# Connectors.net
KiCad netlist of a schematic drawn in Altium Designer
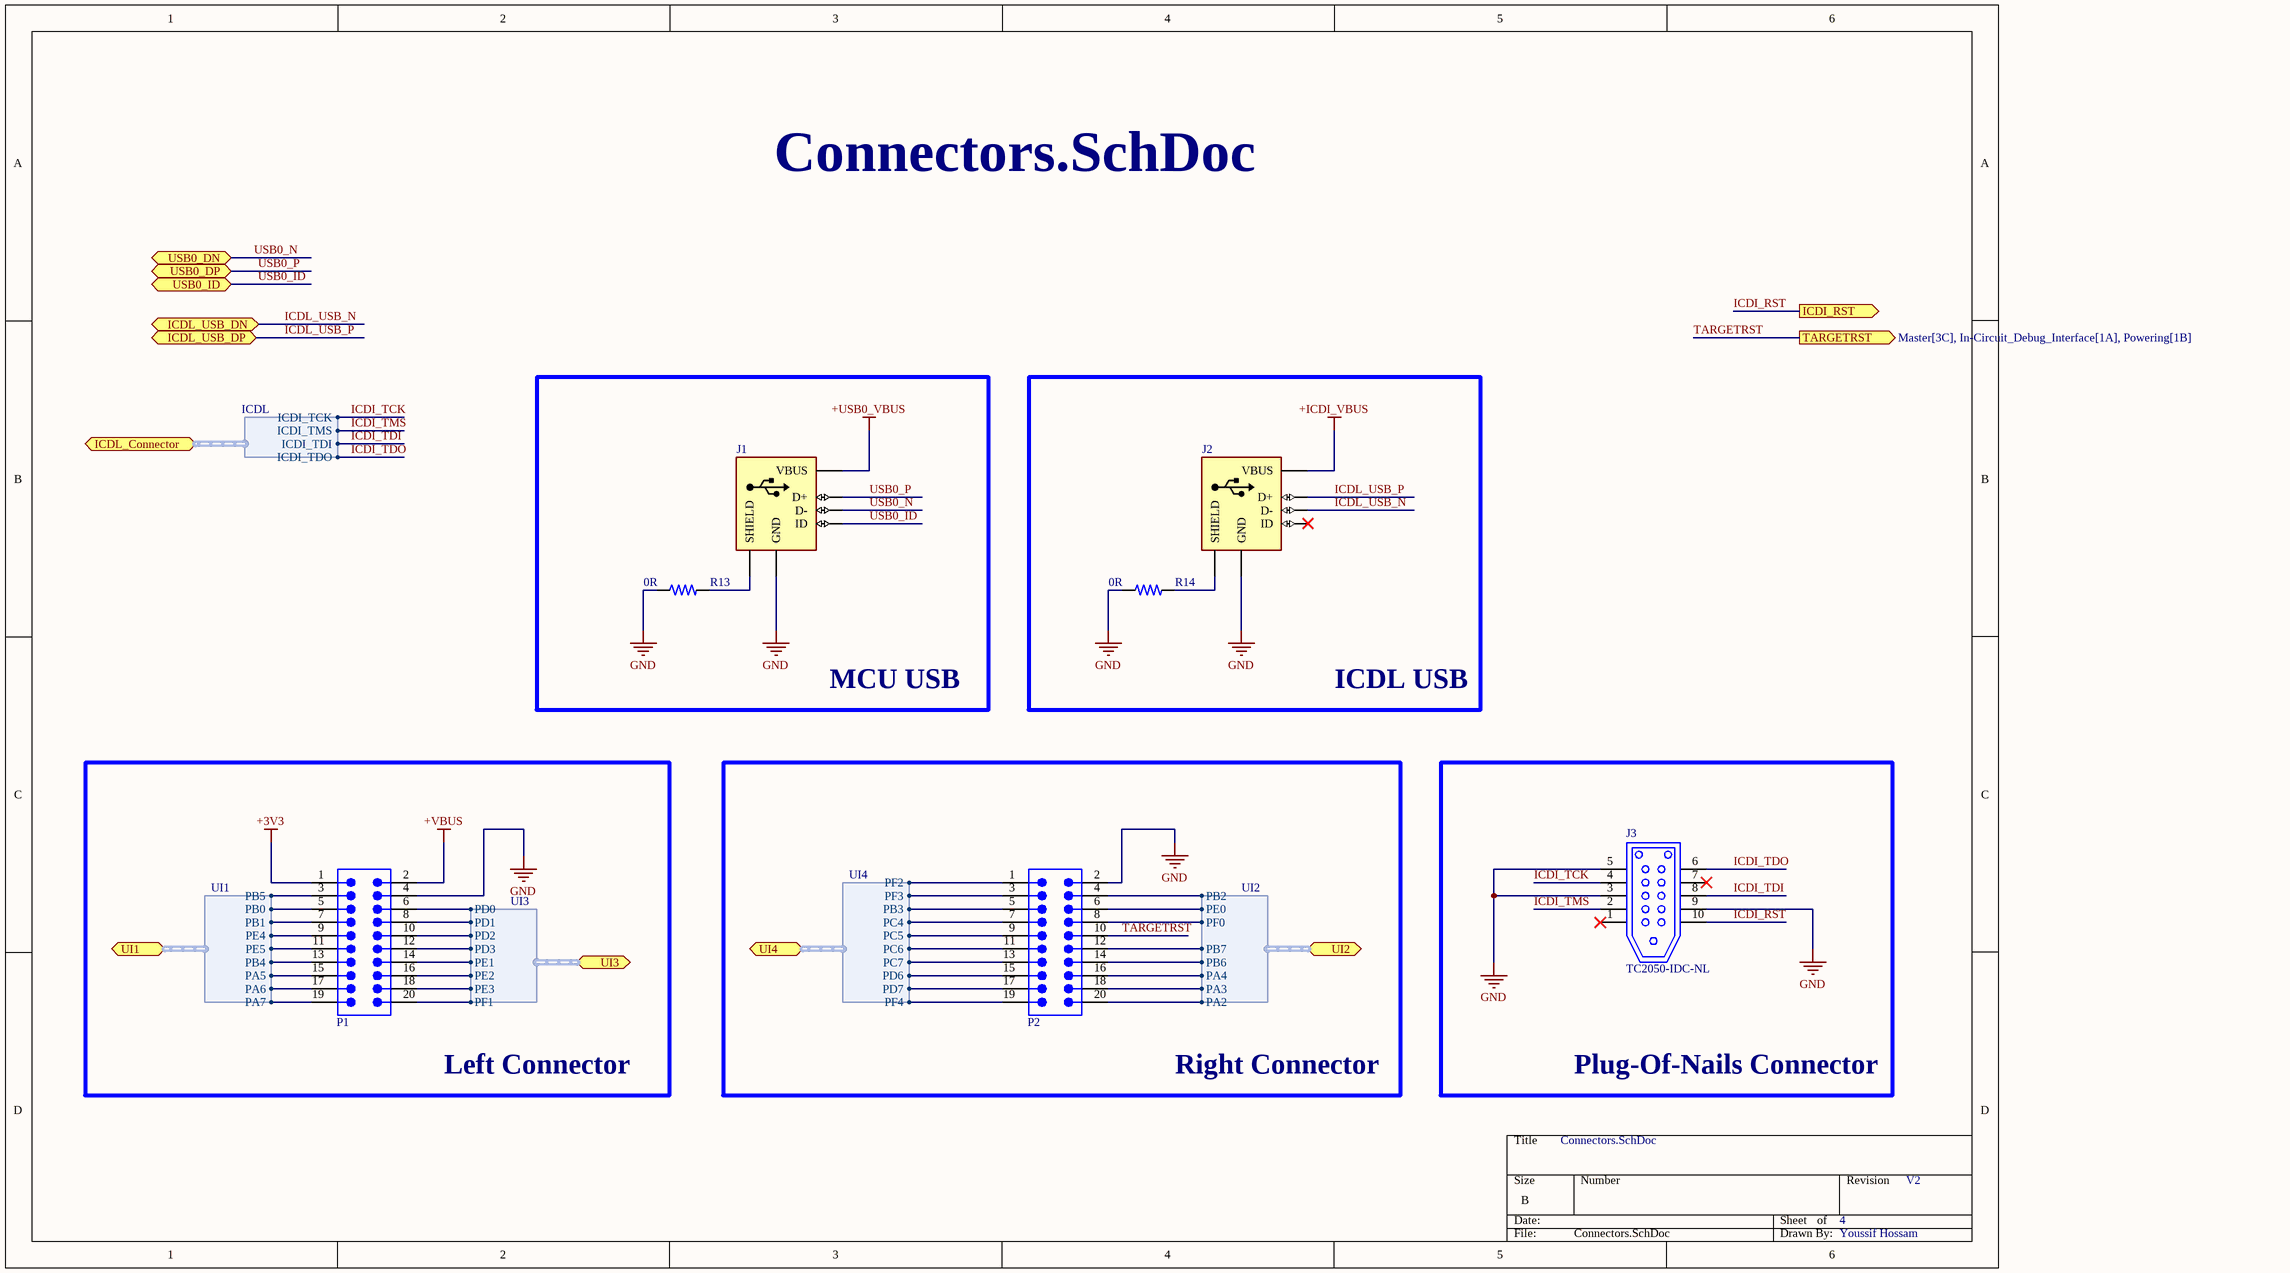
[diagram p0: Connectors.SchDoc]

(export (version "E")
  (design (tool "Eeschema 10.0.6"))
  (components
    (comp (ref "J1")
      (value "USB3085-XX-X_REVD")
      (footprint "GCT_USB3085-XX-X_REVD")
      (description "USB - micro AB USB 2.0 Receptacle Connector 5 Position Surface Mount, Right Angle")
      (fields (field (name "MF") "Global Connector Technology") (field (name "MP") "USB3085-30-A"))
      (libsource (lib "Integrated_Library") (part "USB3085-XX-X_REVD"))
    )
    (comp (ref "J2")
      (value "USB3085-XX-X_REVD")
      (footprint "GCT_USB3085-XX-X_REVD")
      (description "USB - micro AB USB 2.0 Receptacle Connector 5 Position Surface Mount, Right Angle")
      (fields (field (name "MF") "Global Connector Technology") (field (name "MP") "USB3085-30-A"))
      (libsource (lib "Integrated_Library") (part "USB3085-XX-X_REVD"))
    )
    (comp (ref "J3")
      (value "TC2050-IDC-NL")
      (footprint "TAG-CONNECT_TC2050-IDC-NL")
      (description "MSP-FET430 Flash Emulation Tool Plug-Of-Nailsâ„¢ Adapter Cable")
      (fields (field (name "MF") "Tag-Connect LLC"))
      (libsource (lib "Integrated_Library") (part "TC2050-IDC-NL"))
    )
    (comp (ref "P1")
      (value "61302021121")
      (footprint "61302021121")
      (description "WR-PHD Pin Header, THT, Vertical, pitch 2.54mm, 2 Row, 20P")
      (fields (field (name "MANUFACTURER") "Wurth Elektronik"))
      (libsource (lib "Altium_WR-PHD_rev24a") (part "61302021121"))
    )
    (comp (ref "P2")
      (value "61302021121")
      (footprint "61302021121")
      (description "WR-PHD Pin Header, THT, Vertical, pitch 2.54mm, 2 Row, 20P")
      (fields (field (name "MANUFACTURER") "Wurth Elektronik"))
      (libsource (lib "Altium_WR-PHD_rev24a") (part "61302021121"))
    )
    (comp (ref "R13")
      (value "0R")
      (footprint "FP-ERA3A-IPC_B")
      (description "Fixed Resistor, Metal Glaze/thick Film, 0.1W, 0ohm, Surface Mount, 0603")
      (fields
        (field (name "MANUFACTURER") "Panasonic")
        (field (name "MANUFACTURER PART NUMBER") "ERJ-3GEY0R00V")
      )
      (libsource (lib "Integrated_Library") (part "0603 SMD RES"))
    )
    (comp (ref "R14")
      (value "0R")
      (footprint "FP-ERA3A-IPC_B")
      (description "Fixed Resistor, Metal Glaze/thick Film, 0.1W, 0ohm, Surface Mount, 0603")
      (fields
        (field (name "MANUFACTURER") "Panasonic")
        (field (name "MANUFACTURER PART NUMBER") "ERJ-3GEY0R00V")
      )
      (libsource (lib "Integrated_Library") (part "0603 SMD RES"))
    )
  )
  (nets
    (net (code "6") (name "+3V3") (class "Default")
      (node (ref "P1") (pin "1") (pinfunction "1_1") (pintype "passive"))
    )
    (net (code "7") (name "+ICDI_VBUS") (class "Default")
      (node (ref "J2") (pin "1") (pinfunction "VBUS_1") (pintype "power_in"))
    )
    (net (code "8") (name "+USB0_VBUS") (class "Default")
      (node (ref "J1") (pin "1") (pinfunction "VBUS_1") (pintype "power_in"))
    )
    (net (code "9") (name "+VBUS") (class "Default")
      (node (ref "P1") (pin "2") (pinfunction "2_2") (pintype "passive"))
    )
    (net (code "10") (name "/ICDI_RST") (class "Default")
      (node (ref "J3") (pin "10") (pinfunction "10_10") (pintype "passive"))
    )
    (net (code "11") (name "/ICDI_TCK") (class "Default")
      (node (ref "J3") (pin "4") (pinfunction "4_4") (pintype "passive"))
    )
    (net (code "12") (name "/ICDI_TDI") (class "Default")
      (node (ref "J3") (pin "8") (pinfunction "8_8") (pintype "passive"))
    )
    (net (code "13") (name "/ICDI_TDO") (class "Default")
      (node (ref "J3") (pin "6") (pinfunction "6_6") (pintype "passive"))
    )
    (net (code "14") (name "/ICDI_TMS") (class "Default")
      (node (ref "J3") (pin "2") (pinfunction "2_2") (pintype "passive"))
    )
    (net (code "15") (name "/ICDL_USB_N") (class "Default")
      (node (ref "J2") (pin "2") (pinfunction "D-_2") (pintype "bidirectional"))
    )
    (net (code "16") (name "/ICDL_USB_P") (class "Default")
      (node (ref "J2") (pin "3") (pinfunction "D+_3") (pintype "bidirectional"))
    )
    (net (code "17") (name "/PA2") (class "Default")
      (node (ref "P2") (pin "20") (pinfunction "20_20") (pintype "passive"))
    )
    (net (code "18") (name "/PA3") (class "Default")
      (node (ref "P2") (pin "18") (pinfunction "18_18") (pintype "passive"))
    )
    (net (code "19") (name "/PA4") (class "Default")
      (node (ref "P2") (pin "16") (pinfunction "16_16") (pintype "passive"))
    )
    (net (code "20") (name "/PA5") (class "Default")
      (node (ref "P1") (pin "15") (pinfunction "15_15") (pintype "passive"))
    )
    (net (code "21") (name "/PA6") (class "Default")
      (node (ref "P1") (pin "17") (pinfunction "17_17") (pintype "passive"))
    )
    (net (code "22") (name "/PA7") (class "Default")
      (node (ref "P1") (pin "19") (pinfunction "19_19") (pintype "passive"))
    )
    (net (code "23") (name "/PB0") (class "Default")
      (node (ref "P1") (pin "5") (pinfunction "5_5") (pintype "passive"))
    )
    (net (code "24") (name "/PB1") (class "Default")
      (node (ref "P1") (pin "7") (pinfunction "7_7") (pintype "passive"))
    )
    (net (code "25") (name "/PB2") (class "Default")
      (node (ref "P2") (pin "4") (pinfunction "4_4") (pintype "passive"))
    )
    (net (code "26") (name "/PB3") (class "Default")
      (node (ref "P2") (pin "5") (pinfunction "5_5") (pintype "passive"))
    )
    (net (code "27") (name "/PB4") (class "Default")
      (node (ref "P1") (pin "13") (pinfunction "13_13") (pintype "passive"))
    )
    (net (code "28") (name "/PB5") (class "Default")
      (node (ref "P1") (pin "3") (pinfunction "3_3") (pintype "passive"))
    )
    (net (code "29") (name "/PB6") (class "Default")
      (node (ref "P2") (pin "14") (pinfunction "14_14") (pintype "passive"))
    )
    (net (code "30") (name "/PB7") (class "Default")
      (node (ref "P2") (pin "12") (pinfunction "12_12") (pintype "passive"))
    )
    (net (code "31") (name "/PC4") (class "Default")
      (node (ref "P2") (pin "7") (pinfunction "7_7") (pintype "passive"))
    )
    (net (code "32") (name "/PC5") (class "Default")
      (node (ref "P2") (pin "9") (pinfunction "9_9") (pintype "passive"))
    )
    (net (code "33") (name "/PC6") (class "Default")
      (node (ref "P2") (pin "11") (pinfunction "11_11") (pintype "passive"))
    )
    (net (code "34") (name "/PC7") (class "Default")
      (node (ref "P2") (pin "13") (pinfunction "13_13") (pintype "passive"))
    )
    (net (code "35") (name "/PD0") (class "Default")
      (node (ref "P1") (pin "6") (pinfunction "6_6") (pintype "passive"))
    )
    (net (code "36") (name "/PD1") (class "Default")
      (node (ref "P1") (pin "8") (pinfunction "8_8") (pintype "passive"))
    )
    (net (code "37") (name "/PD2") (class "Default")
      (node (ref "P1") (pin "10") (pinfunction "10_10") (pintype "passive"))
    )
    (net (code "38") (name "/PD3") (class "Default")
      (node (ref "P1") (pin "12") (pinfunction "12_12") (pintype "passive"))
    )
    (net (code "39") (name "/PD6") (class "Default")
      (node (ref "P2") (pin "15") (pinfunction "15_15") (pintype "passive"))
    )
    (net (code "40") (name "/PD7") (class "Default")
      (node (ref "P2") (pin "17") (pinfunction "17_17") (pintype "passive"))
    )
    (net (code "41") (name "/PE0") (class "Default")
      (node (ref "P2") (pin "6") (pinfunction "6_6") (pintype "passive"))
    )
    (net (code "42") (name "/PE1") (class "Default")
      (node (ref "P1") (pin "14") (pinfunction "14_14") (pintype "passive"))
    )
    (net (code "43") (name "/PE2") (class "Default")
      (node (ref "P1") (pin "16") (pinfunction "16_16") (pintype "passive"))
    )
    (net (code "44") (name "/PE3") (class "Default")
      (node (ref "P1") (pin "18") (pinfunction "18_18") (pintype "passive"))
    )
    (net (code "45") (name "/PE4") (class "Default")
      (node (ref "P1") (pin "9") (pinfunction "9_9") (pintype "passive"))
    )
    (net (code "46") (name "/PE5") (class "Default")
      (node (ref "P1") (pin "11") (pinfunction "11_11") (pintype "passive"))
    )
    (net (code "47") (name "/PF0") (class "Default")
      (node (ref "P2") (pin "8") (pinfunction "8_8") (pintype "passive"))
    )
    (net (code "48") (name "/PF1") (class "Default")
      (node (ref "P1") (pin "20") (pinfunction "20_20") (pintype "passive"))
    )
    (net (code "49") (name "/PF2") (class "Default")
      (node (ref "P2") (pin "1") (pinfunction "1_1") (pintype "passive"))
    )
    (net (code "50") (name "/PF3") (class "Default")
      (node (ref "P2") (pin "3") (pinfunction "3_3") (pintype "passive"))
    )
    (net (code "51") (name "/PF4") (class "Default")
      (node (ref "P2") (pin "19") (pinfunction "19_19") (pintype "passive"))
    )
    (net (code "52") (name "/TARGETRST") (class "Default")
      (node (ref "P2") (pin "10") (pinfunction "10_10") (pintype "passive"))
    )
    (net (code "53") (name "/USB0_ID") (class "Default")
      (node (ref "J1") (pin "4") (pinfunction "ID_4") (pintype "bidirectional"))
    )
    (net (code "54") (name "/USB0_N") (class "Default")
      (node (ref "J1") (pin "2") (pinfunction "D-_2") (pintype "bidirectional"))
    )
    (net (code "55") (name "/USB0_P") (class "Default")
      (node (ref "J1") (pin "3") (pinfunction "D+_3") (pintype "bidirectional"))
    )
    (net (code "61") (name "GND") (class "Default")
      (node (ref "J1") (pin "5") (pinfunction "GND_5") (pintype "power_in"))
      (node (ref "J2") (pin "5") (pinfunction "GND_5") (pintype "power_in"))
      (node (ref "J3") (pin "3") (pinfunction "3_3") (pintype "passive"))
      (node (ref "J3") (pin "5") (pinfunction "5_5") (pintype "passive"))
      (node (ref "J3") (pin "9") (pinfunction "9_9") (pintype "passive"))
      (node (ref "P1") (pin "4") (pinfunction "4_4") (pintype "passive"))
      (node (ref "P2") (pin "2") (pinfunction "2_2") (pintype "passive"))
      (node (ref "R13") (pin "1") (pinfunction "1_1") (pintype "passive"))
      (node (ref "R14") (pin "1") (pinfunction "1_1") (pintype "passive"))
    )
    (net (code "62") (name "Net-(J1-SHIELD)") (class "Default")
      (node (ref "J1") (pin "SH") (pinfunction "SHIELD_SH") (pintype "passive"))
      (node (ref "R13") (pin "2") (pinfunction "2_2") (pintype "passive"))
    )
    (net (code "63") (name "Net-(J2-SHIELD)") (class "Default")
      (node (ref "J2") (pin "SH") (pinfunction "SHIELD_SH") (pintype "passive"))
      (node (ref "R14") (pin "2") (pinfunction "2_2") (pintype "passive"))
    )
    (net (code "64") (name "unconnected-(J2-ID-Pad4)") (class "Default")
      (node (ref "J2") (pin "4") (pinfunction "ID_4") (pintype "bidirectional+no_connect"))
    )
    (net (code "65") (name "unconnected-(J3-Pad1)") (class "Default")
      (node (ref "J3") (pin "1") (pinfunction "1_1") (pintype "passive+no_connect"))
    )
    (net (code "66") (name "unconnected-(J3-Pad7)") (class "Default")
      (node (ref "J3") (pin "7") (pinfunction "7_7") (pintype "passive+no_connect"))
    )
  )
)
